# Barometer_022.net
KiCad netlist of a schematic drawn in EAGLE
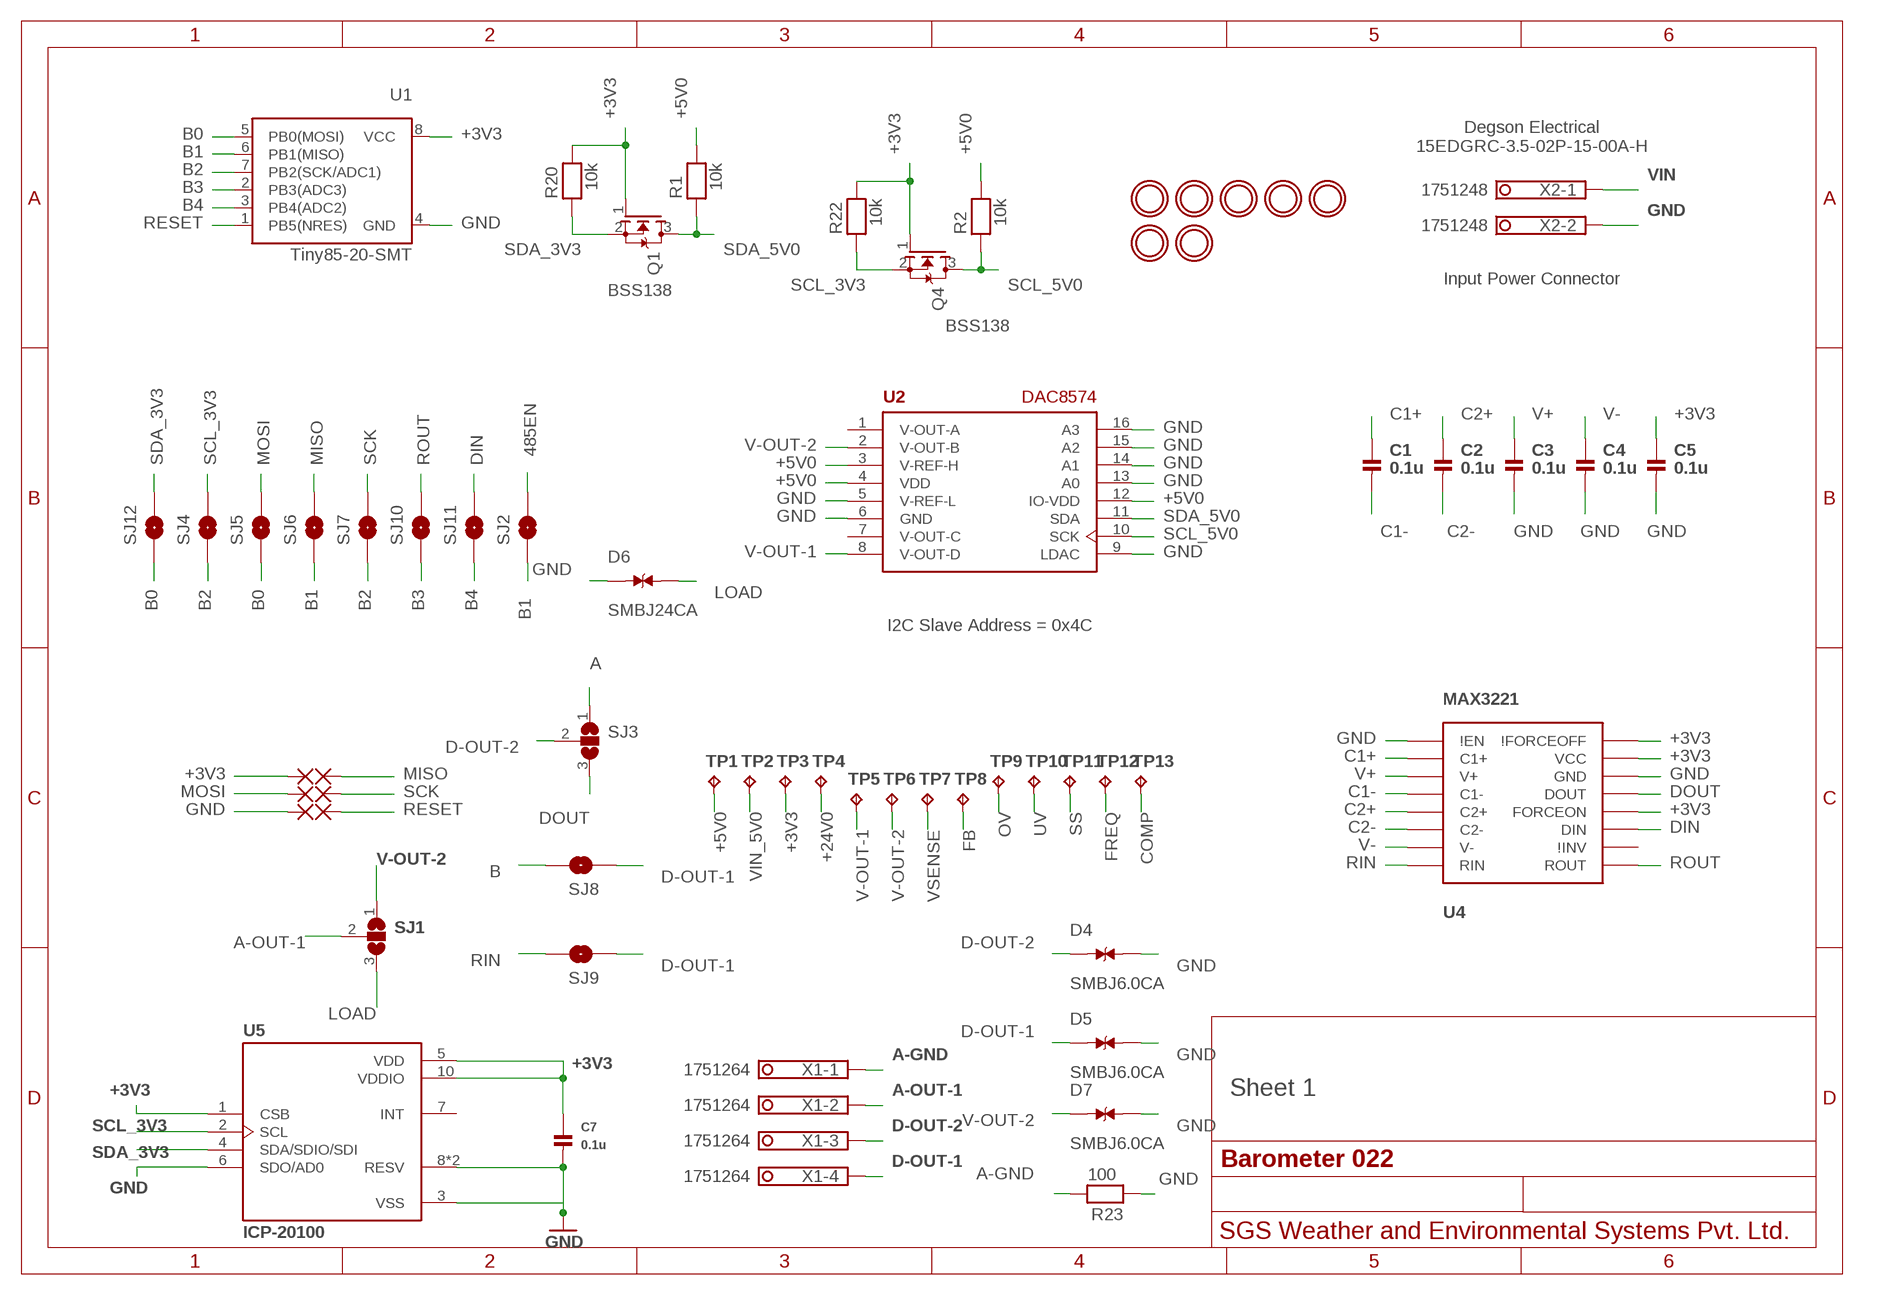
[diagram p0: schematic, sheet 1]
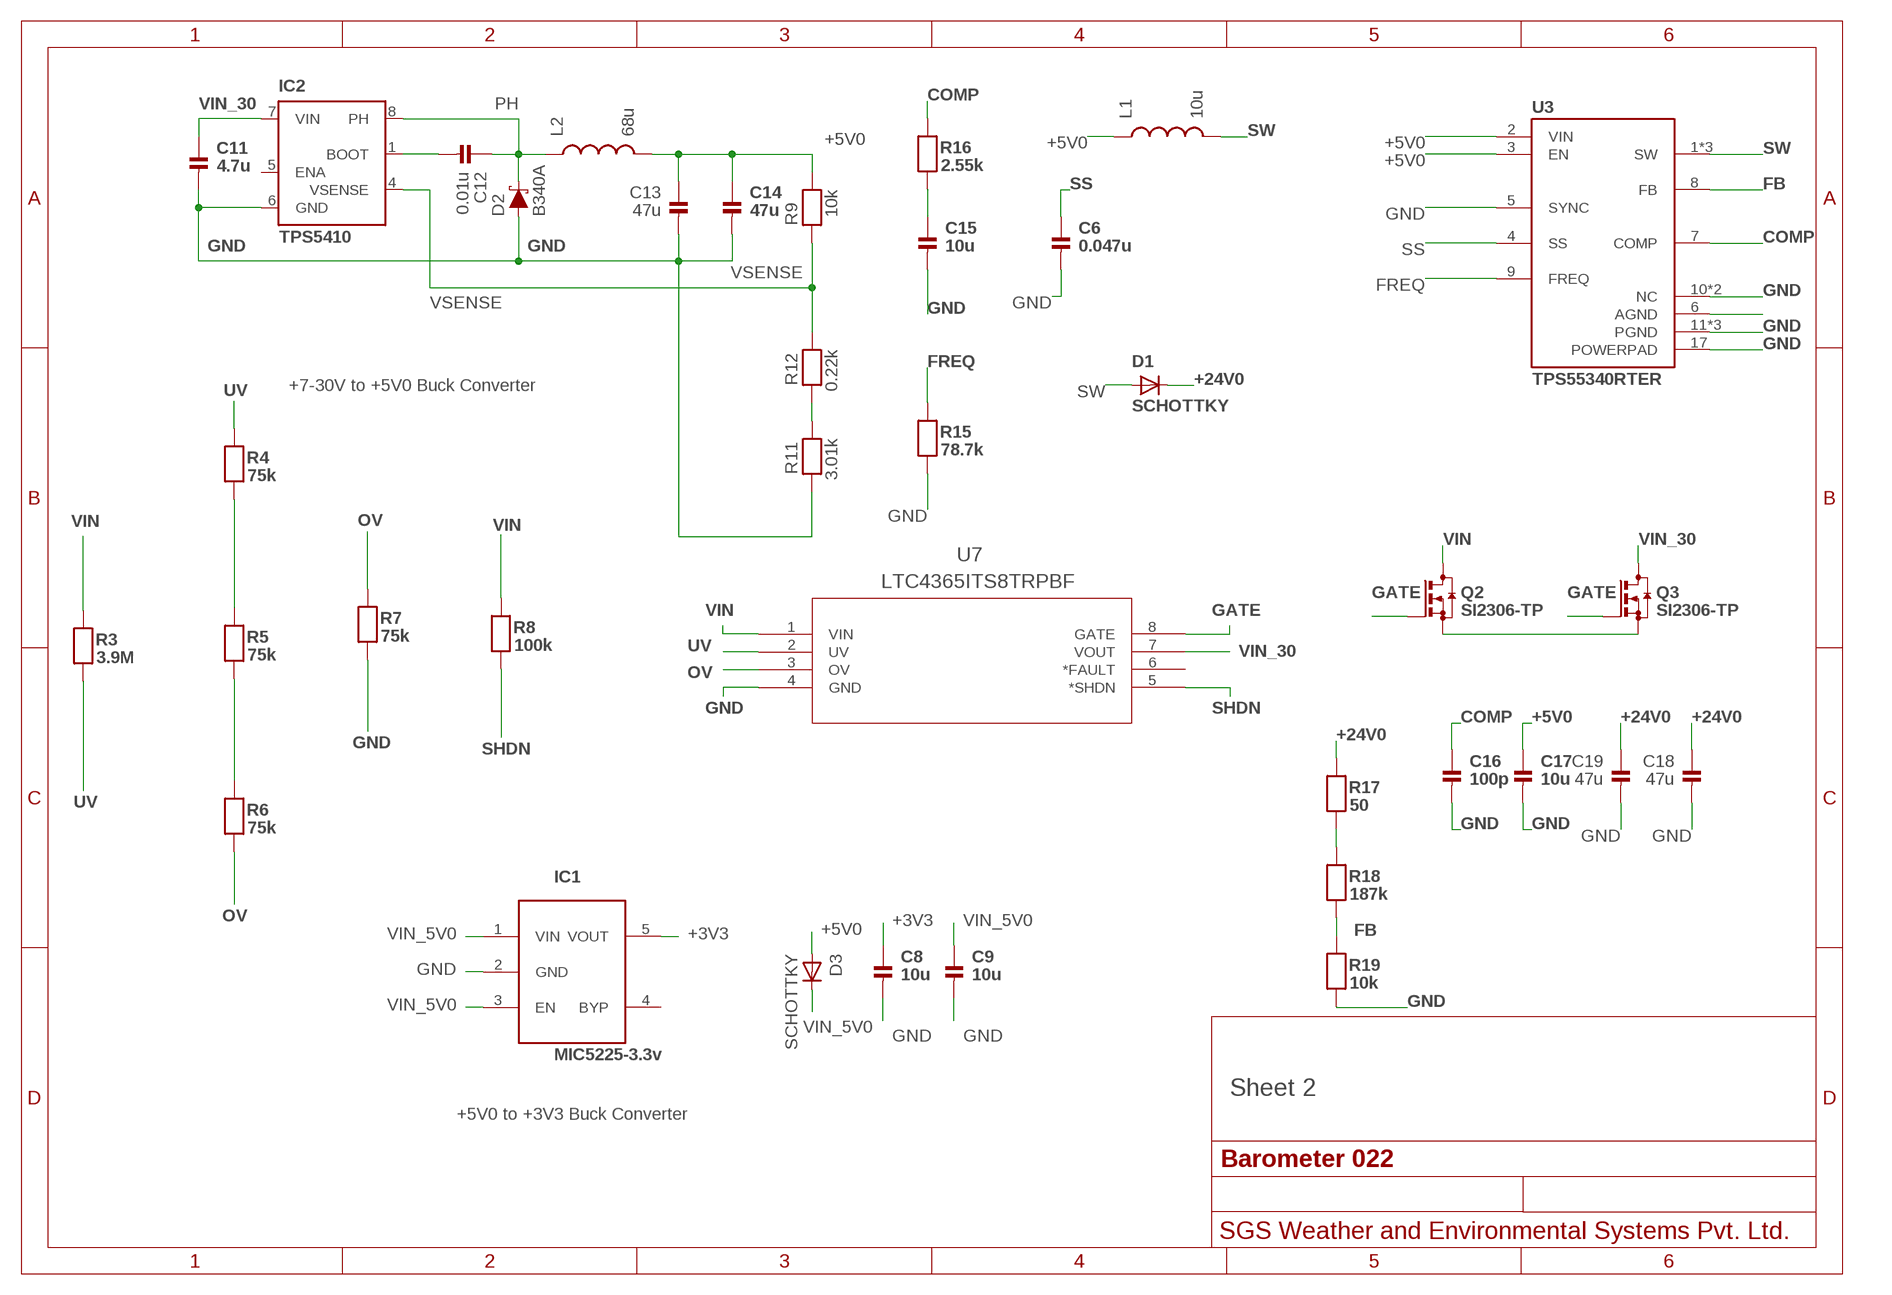
[diagram p1: schematic, sheet 2]
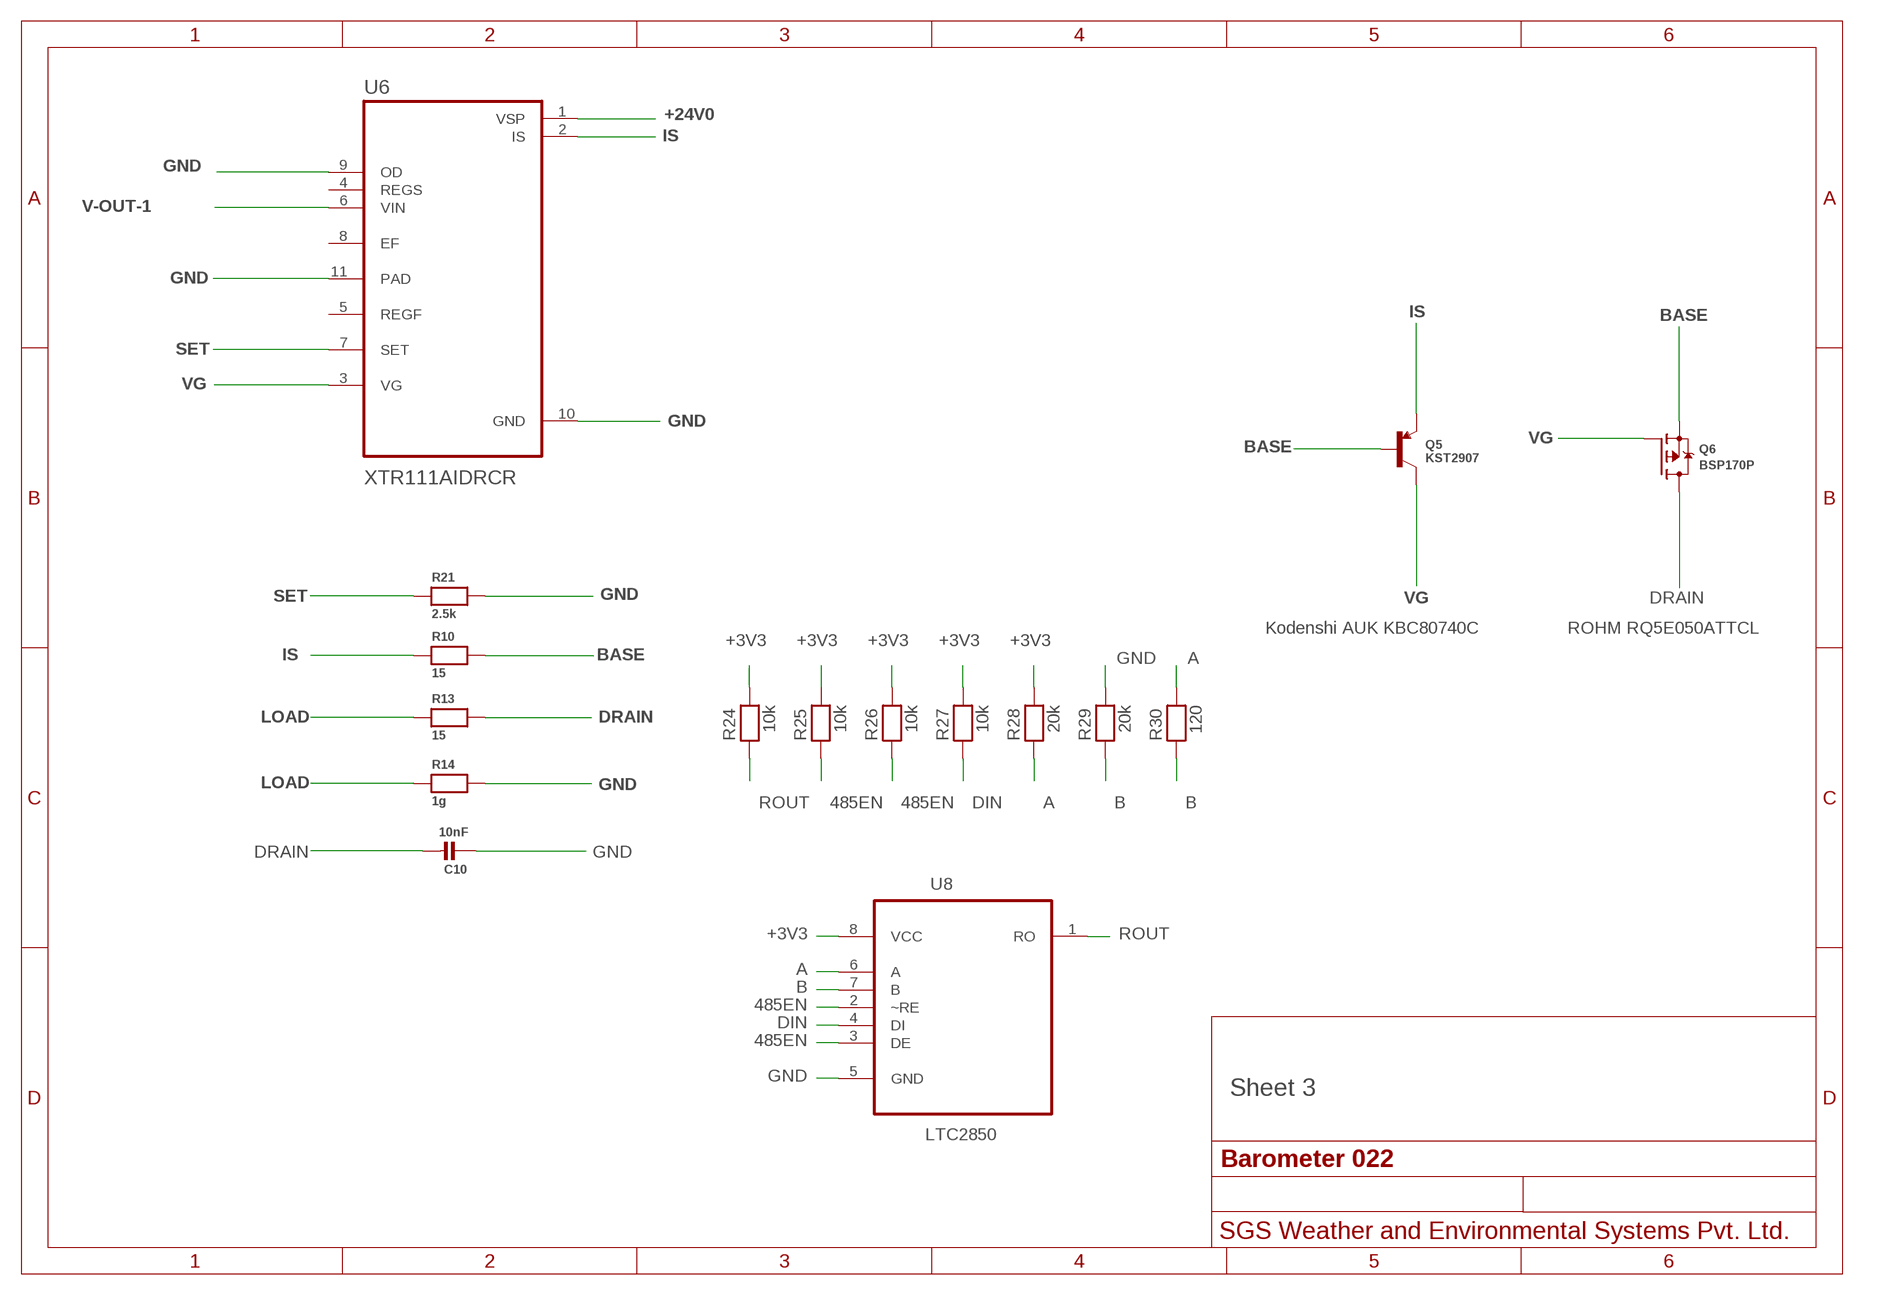
[diagram p2: schematic, sheet 3]
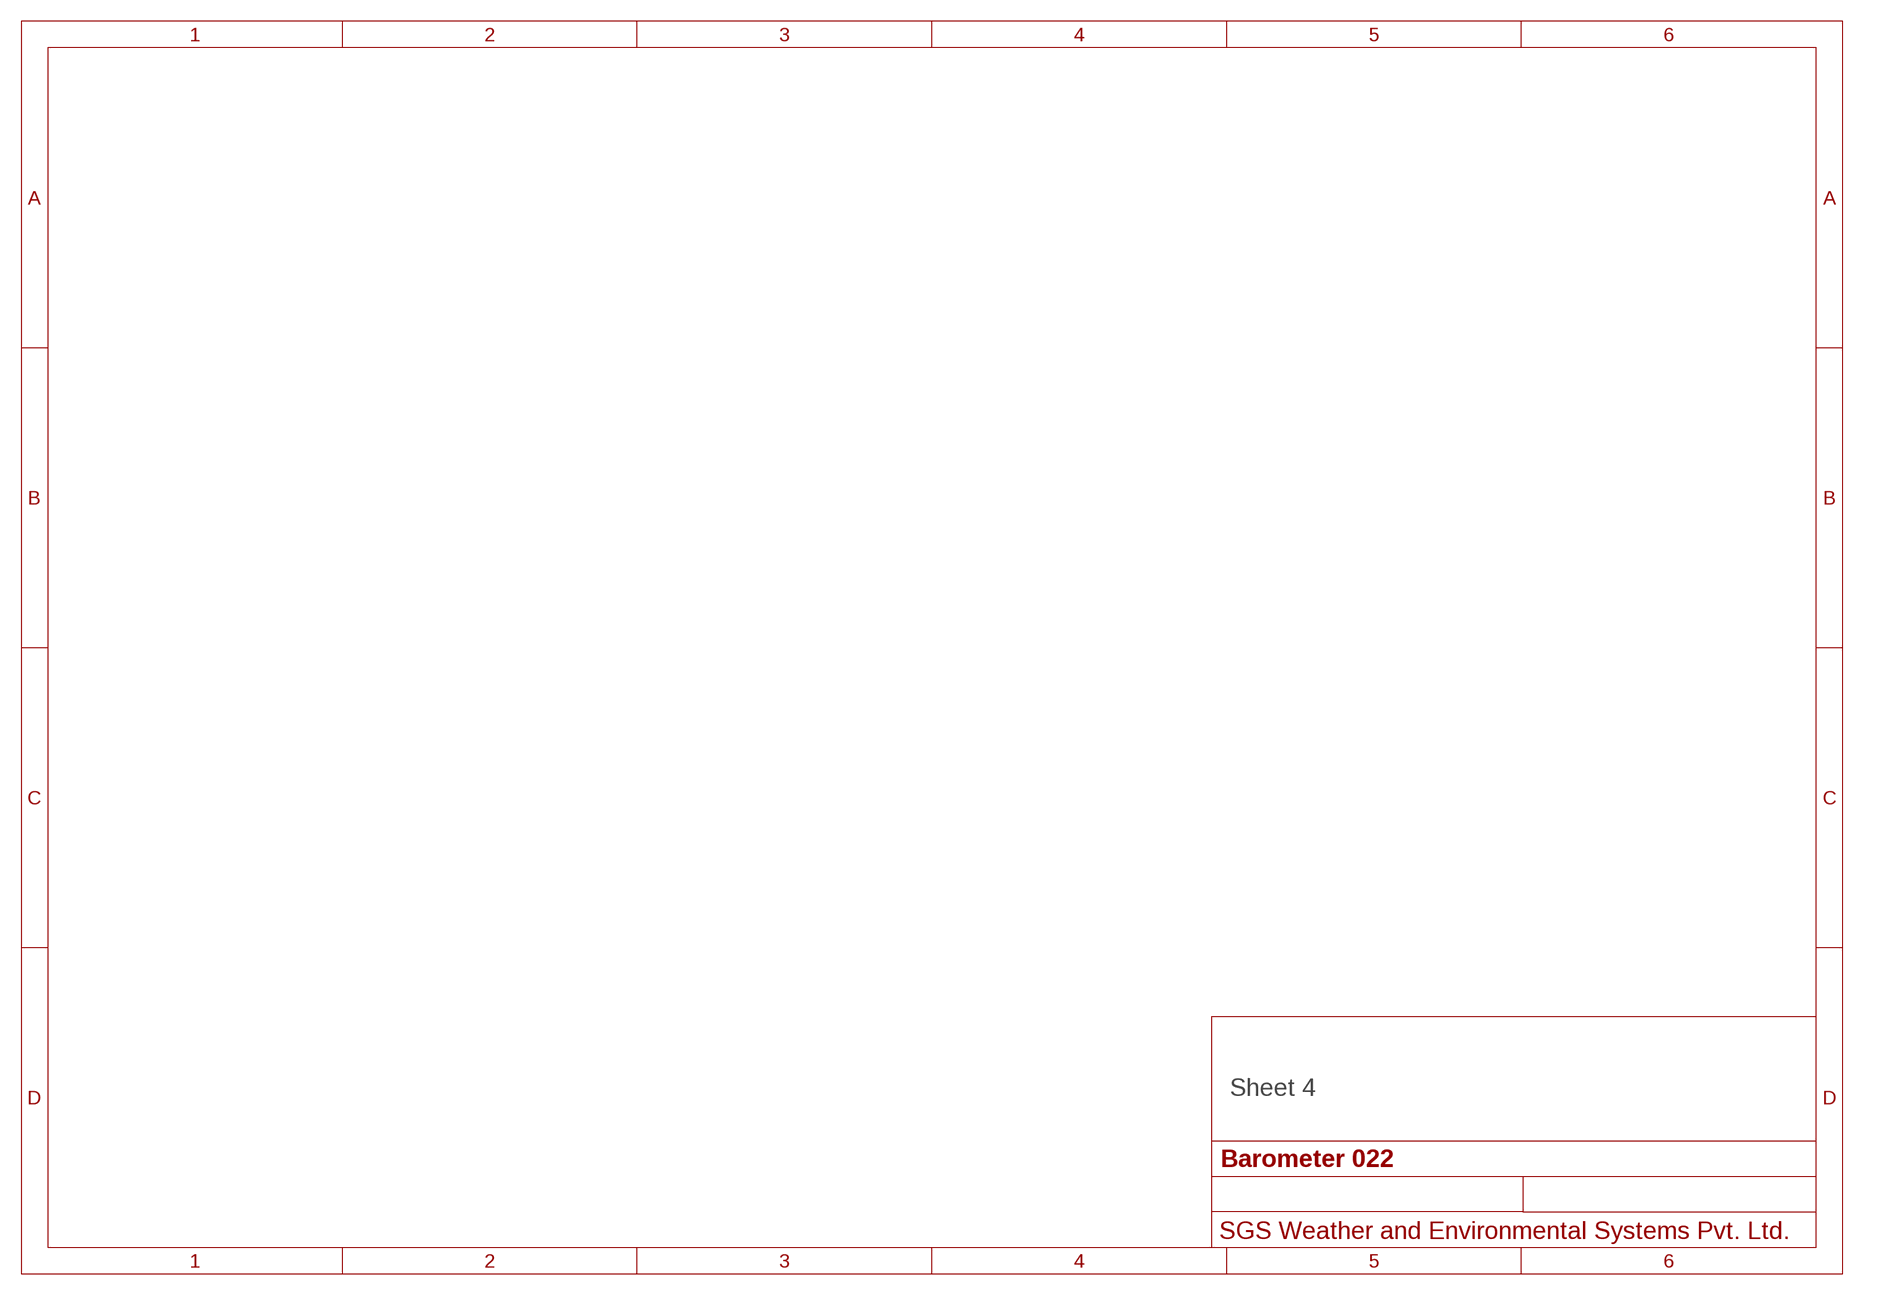
[diagram p3: schematic, sheet 4]

(export (version "E")
  (design (tool "Eeschema 10.0.6"))
  (components
    (comp (ref "C6")
      (value "0.047u")
      (footprint "eagle-import:0603@1")
      (libsource (lib "eagle-import") (part "CAP_CERAMIC0603"))
    )
    (comp (ref "C8")
      (value "10u")
      (footprint "eagle-import:0603@1")
      (libsource (lib "eagle-import") (part "CAP_CERAMIC0603"))
    )
    (comp (ref "C9")
      (value "10u")
      (footprint "eagle-import:0603@1")
      (libsource (lib "eagle-import") (part "CAP_CERAMIC0603"))
    )
    (comp (ref "C11")
      (value "4.7u")
      (footprint "eagle-import:0805@1")
      (libsource (lib "eagle-import") (part "CAP_CERAMIC0805"))
    )
    (comp (ref "C12")
      (value "0.01u")
      (footprint "eagle-import:0603@1")
      (libsource (lib "eagle-import") (part "CAP_CERAMIC0603"))
    )
    (comp (ref "C13")
      (value "47u")
      (footprint "eagle-import:1206@1")
      (libsource (lib "eagle-import") (part "CAP_CERAMIC1206"))
    )
    (comp (ref "C14")
      (value "47u")
      (footprint "eagle-import:1206@1")
      (libsource (lib "eagle-import") (part "CAP_CERAMIC1206"))
    )
    (comp (ref "C15")
      (value "10u")
      (footprint "eagle-import:0603@1")
      (libsource (lib "eagle-import") (part "CAP_CERAMIC0603"))
    )
    (comp (ref "C16")
      (value "100p")
      (footprint "eagle-import:0603@1")
      (libsource (lib "eagle-import") (part "CAP_CERAMIC0603"))
    )
    (comp (ref "C17")
      (value "10u")
      (footprint "eagle-import:0603@1")
      (libsource (lib "eagle-import") (part "CAP_CERAMIC0603"))
    )
    (comp (ref "C18")
      (value "47u")
      (footprint "eagle-import:1206@1")
      (libsource (lib "eagle-import") (part "CAP_CERAMIC1206"))
    )
    (comp (ref "C19")
      (value "47u")
      (footprint "eagle-import:1206@1")
      (libsource (lib "eagle-import") (part "CAP_CERAMIC1206"))
    )
    (comp (ref "D1")
      (value "SCHOTTKY")
      (footprint "eagle-import:SOD-123FL")
      (libsource (lib "eagle-import") (part "DIODE_SOD-123FL"))
    )
    (comp (ref "D2")
      (value "B340A")
      (footprint "eagle-import:SMA-DIODE")
      (libsource (lib "eagle-import") (part "DIODE-SCHOTTKY-B340A"))
    )
    (comp (ref "D3")
      (value "SCHOTTKY")
      (footprint "eagle-import:SOD-123FL")
      (libsource (lib "eagle-import") (part "DIODE_SOD-123FL"))
    )
    (comp (ref "IC1")
      (value "MIC5225-3.3v")
      (footprint "eagle-import:SOT23-5L")
      (libsource (lib "eagle-import") (part "LP298XS"))
    )
    (comp (ref "IC2")
      (value "TPS5410")
      (footprint "eagle-import:D_R-PDSO-G08")
      (fields (field (name "MPN") "TPS5410DR"))
      (libsource (lib "eagle-import") (part "TPS5410"))
    )
    (comp (ref "L1")
      (value "10u")
      (footprint "eagle-import:VLS6045EX")
      (libsource (lib "eagle-import") (part "INDUCTOR-TDKVLS6045EX"))
    )
    (comp (ref "L2")
      (value "68u")
      (footprint "eagle-import:VLS6045EX")
      (libsource (lib "eagle-import") (part "INDUCTOR-TDKVLS6045EX"))
    )
    (comp (ref "Q2")
      (value "SI2306-TP")
      (footprint "eagle-import:SOT23")
      (libsource (lib "eagle-import") (part "BSS123"))
    )
    (comp (ref "Q3")
      (value "SI2306-TP")
      (footprint "eagle-import:SOT23")
      (libsource (lib "eagle-import") (part "BSS123"))
    )
    (comp (ref "R3")
      (value "3.9M")
      (footprint "eagle-import:0603")
      (libsource (lib "eagle-import") (part "RESISTOR0603"))
    )
    (comp (ref "R4")
      (value "75k")
      (footprint "eagle-import:0603")
      (libsource (lib "eagle-import") (part "RESISTOR0603"))
    )
    (comp (ref "R5")
      (value "75k")
      (footprint "eagle-import:0603")
      (libsource (lib "eagle-import") (part "RESISTOR0603"))
    )
    (comp (ref "R6")
      (value "75k")
      (footprint "eagle-import:0603")
      (libsource (lib "eagle-import") (part "RESISTOR0603"))
    )
    (comp (ref "R7")
      (value "75k")
      (footprint "eagle-import:0603")
      (libsource (lib "eagle-import") (part "RESISTOR0603"))
    )
    (comp (ref "R8")
      (value "100k")
      (footprint "eagle-import:0603")
      (libsource (lib "eagle-import") (part "RESISTOR0603"))
    )
    (comp (ref "R9")
      (value "10k")
      (footprint "eagle-import:0603")
      (libsource (lib "eagle-import") (part "RESISTOR0603"))
    )
    (comp (ref "R11")
      (value "3.01k")
      (footprint "eagle-import:0603")
      (libsource (lib "eagle-import") (part "RESISTOR0603"))
    )
    (comp (ref "R12")
      (value "0.22k")
      (footprint "eagle-import:0603")
      (libsource (lib "eagle-import") (part "RESISTOR0603"))
    )
    (comp (ref "R15")
      (value "78.7k")
      (footprint "eagle-import:0603")
      (libsource (lib "eagle-import") (part "RESISTOR0603"))
    )
    (comp (ref "R16")
      (value "2.55k")
      (footprint "eagle-import:0603")
      (libsource (lib "eagle-import") (part "RESISTOR0603"))
    )
    (comp (ref "R17")
      (value "50")
      (footprint "eagle-import:0603")
      (libsource (lib "eagle-import") (part "RESISTOR0603"))
    )
    (comp (ref "R18")
      (value "187k")
      (footprint "eagle-import:0603")
      (libsource (lib "eagle-import") (part "RESISTOR0603"))
    )
    (comp (ref "R19")
      (value "10k")
      (footprint "eagle-import:0603")
      (libsource (lib "eagle-import") (part "RESISTOR0603"))
    )
    (comp (ref "U3")
      (value "TPS55340RTER")
      (footprint "eagle-import:QFN50P300X300X80-17N")
      (fields (field (name "MF") "Texas Instruments"))
      (libsource (lib "eagle-import") (part "TPS55340RTER"))
    )
    (comp (ref "U7")
      (value "LTC4365ITS8TRPBF")
      (footprint "eagle-import:TSOT-23_TS8")
      (fields (field (name "MF") "Analog Devices") (field (name "MP") "LTC4365ITS8#TRPBF"))
      (libsource (lib "eagle-import") (part "LTC4365ITS8TRPBF"))
    )
    (comp (ref "C1")
      (value "0.1u")
      (footprint "eagle-import:0603@1")
      (libsource (lib "eagle-import") (part "CAP_CERAMIC0603"))
    )
    (comp (ref "C2")
      (value "0.1u")
      (footprint "eagle-import:0603@1")
      (libsource (lib "eagle-import") (part "CAP_CERAMIC0603"))
    )
    (comp (ref "C3")
      (value "0.1u")
      (footprint "eagle-import:0603@1")
      (libsource (lib "eagle-import") (part "CAP_CERAMIC0603"))
    )
    (comp (ref "C4")
      (value "0.1u")
      (footprint "eagle-import:0603@1")
      (libsource (lib "eagle-import") (part "CAP_CERAMIC0603"))
    )
    (comp (ref "C5")
      (value "0.1u")
      (footprint "eagle-import:0603@1")
      (libsource (lib "eagle-import") (part "CAP_CERAMIC0603"))
    )
    (comp (ref "C7")
      (value "0.1u")
      (footprint "eagle-import:0603@1")
      (libsource (lib "eagle-import") (part "CAP_CERAMIC0603"))
    )
    (comp (ref "D4")
      (value "SMBJ6.0CA")
      (footprint "eagle-import:DIOM4336X265N")
      (fields (field (name "MF") "Bourns"))
      (libsource (lib "eagle-import") (part "SMBJ6.0CA"))
    )
    (comp (ref "D5")
      (value "SMBJ6.0CA")
      (footprint "eagle-import:DIOM4336X265N")
      (fields (field (name "MF") "Bourns"))
      (libsource (lib "eagle-import") (part "SMBJ6.0CA"))
    )
    (comp (ref "D6")
      (value "SMBJ24CA")
      (footprint "eagle-import:DIOM4336X265N")
      (fields
        (field (name "DIGI-KEY_PART_NUMBER") "SMBJ24CAFSTR-ND")
        (field (name "MF") "Taiwan Semiconductor")
      )
      (libsource (lib "eagle-import") (part "SMBJ24CA"))
    )
    (comp (ref "D7")
      (value "SMBJ6.0CA")
      (footprint "eagle-import:DIOM4336X265N")
      (fields (field (name "MF") "Bourns"))
      (libsource (lib "eagle-import") (part "SMBJ6.0CA"))
    )
    (comp (ref "PAD1")
      (value "SMD2")
      (footprint "eagle-import:SMD1,27-2,54")
      (libsource (lib "eagle-import") (part "SMD2"))
    )
    (comp (ref "PAD2")
      (value "SMD2")
      (footprint "eagle-import:SMD1,27-2,54")
      (libsource (lib "eagle-import") (part "SMD2"))
    )
    (comp (ref "PAD3")
      (value "SMD2")
      (footprint "eagle-import:SMD1,27-2,54")
      (libsource (lib "eagle-import") (part "SMD2"))
    )
    (comp (ref "PAD4")
      (value "SMD2")
      (footprint "eagle-import:SMD1,27-2,54")
      (libsource (lib "eagle-import") (part "SMD2"))
    )
    (comp (ref "PAD5")
      (value "SMD2")
      (footprint "eagle-import:SMD1,27-2,54")
      (libsource (lib "eagle-import") (part "SMD2"))
    )
    (comp (ref "PAD6")
      (value "SMD2")
      (footprint "eagle-import:SMD1,27-2,54")
      (libsource (lib "eagle-import") (part "SMD2"))
    )
    (comp (ref "Q1")
      (value "MOSFET-NWIDE")
      (footprint "eagle-import:SOT23-WIDE")
      (libsource (lib "eagle-import") (part "MOSFET-NWIDE"))
    )
    (comp (ref "Q4")
      (value "MOSFET-NWIDE")
      (footprint "eagle-import:SOT23-WIDE")
      (libsource (lib "eagle-import") (part "MOSFET-NWIDE"))
    )
    (comp (ref "R1")
      (value "10k")
      (footprint "eagle-import:0603")
      (libsource (lib "eagle-import") (part "RESISTOR0603"))
    )
    (comp (ref "R2")
      (value "10k")
      (footprint "eagle-import:0603")
      (libsource (lib "eagle-import") (part "RESISTOR0603"))
    )
    (comp (ref "R20")
      (value "10k")
      (footprint "eagle-import:0603")
      (libsource (lib "eagle-import") (part "RESISTOR0603"))
    )
    (comp (ref "R22")
      (value "10k")
      (footprint "eagle-import:0603")
      (libsource (lib "eagle-import") (part "RESISTOR0603"))
    )
    (comp (ref "R23")
      (value "100")
      (footprint "eagle-import:0603")
      (libsource (lib "eagle-import") (part "RESISTOR0603"))
    )
    (comp (ref "SJ1")
      (value "SJ2WW")
      (footprint "eagle-import:SJ_2W")
      (libsource (lib "eagle-import") (part "SJ2WW"))
    )
    (comp (ref "SJ2")
      (value "SOLDERJUMPERTRACE")
      (footprint "eagle-import:SJ_2S-TRACE")
      (libsource (lib "eagle-import") (part "SOLDERJUMPERTRACE"))
    )
    (comp (ref "SJ3")
      (value "SJ2W")
      (footprint "eagle-import:SJ_2")
      (libsource (lib "eagle-import") (part "SJ2W"))
    )
    (comp (ref "SJ4")
      (value "SOLDERJUMPERTRACE")
      (footprint "eagle-import:SJ_2S-TRACE")
      (libsource (lib "eagle-import") (part "SOLDERJUMPERTRACE"))
    )
    (comp (ref "SJ5")
      (value "SOLDERJUMPERTRACE")
      (footprint "eagle-import:SJ_2S-TRACE")
      (libsource (lib "eagle-import") (part "SOLDERJUMPERTRACE"))
    )
    (comp (ref "SJ6")
      (value "SOLDERJUMPERTRACE")
      (footprint "eagle-import:SJ_2S-TRACE")
      (libsource (lib "eagle-import") (part "SOLDERJUMPERTRACE"))
    )
    (comp (ref "SJ7")
      (value "SOLDERJUMPERTRACE")
      (footprint "eagle-import:SJ_2S-TRACE")
      (libsource (lib "eagle-import") (part "SOLDERJUMPERTRACE"))
    )
    (comp (ref "SJ8")
      (value "SOLDERJUMPERTRACE")
      (footprint "eagle-import:SJ_2S-TRACE")
      (libsource (lib "eagle-import") (part "SOLDERJUMPERTRACE"))
    )
    (comp (ref "SJ9")
      (value "SOLDERJUMPERTRACE")
      (footprint "eagle-import:SJ_2S-TRACE")
      (libsource (lib "eagle-import") (part "SOLDERJUMPERTRACE"))
    )
    (comp (ref "SJ10")
      (value "SOLDERJUMPERTRACE")
      (footprint "eagle-import:SJ_2S-TRACE")
      (libsource (lib "eagle-import") (part "SOLDERJUMPERTRACE"))
    )
    (comp (ref "SJ11")
      (value "SOLDERJUMPERTRACE")
      (footprint "eagle-import:SJ_2S-TRACE")
      (libsource (lib "eagle-import") (part "SOLDERJUMPERTRACE"))
    )
    (comp (ref "SJ12")
      (value "SOLDERJUMPERNO")
      (footprint "eagle-import:SJ_2S-NO")
      (libsource (lib "eagle-import") (part "SOLDERJUMPERNO"))
    )
    (comp (ref "TP1")
      (value "TPB1,27")
      (footprint "eagle-import:B1,27")
      (libsource (lib "eagle-import") (part "TPB1,27"))
    )
    (comp (ref "TP2")
      (value "TPB1,27")
      (footprint "eagle-import:B1,27")
      (libsource (lib "eagle-import") (part "TPB1,27"))
    )
    (comp (ref "TP3")
      (value "TPB1,27")
      (footprint "eagle-import:B1,27")
      (libsource (lib "eagle-import") (part "TPB1,27"))
    )
    (comp (ref "TP4")
      (value "TPB1,27")
      (footprint "eagle-import:B1,27")
      (libsource (lib "eagle-import") (part "TPB1,27"))
    )
    (comp (ref "TP5")
      (value "TPB1,27")
      (footprint "eagle-import:B1,27")
      (libsource (lib "eagle-import") (part "TPB1,27"))
    )
    (comp (ref "TP6")
      (value "TPB1,27")
      (footprint "eagle-import:B1,27")
      (libsource (lib "eagle-import") (part "TPB1,27"))
    )
    (comp (ref "TP7")
      (value "TPB1,27")
      (footprint "eagle-import:B1,27")
      (libsource (lib "eagle-import") (part "TPB1,27"))
    )
    (comp (ref "TP8")
      (value "TPB1,27")
      (footprint "eagle-import:B1,27")
      (libsource (lib "eagle-import") (part "TPB1,27"))
    )
    (comp (ref "TP9")
      (value "TPB1,27")
      (footprint "eagle-import:B1,27")
      (libsource (lib "eagle-import") (part "TPB1,27"))
    )
    (comp (ref "TP10")
      (value "TPB1,27")
      (footprint "eagle-import:B1,27")
      (libsource (lib "eagle-import") (part "TPB1,27"))
    )
    (comp (ref "TP11")
      (value "TPB1,27")
      (footprint "eagle-import:B1,27")
      (libsource (lib "eagle-import") (part "TPB1,27"))
    )
    (comp (ref "TP12")
      (value "TPB1,27")
      (footprint "eagle-import:B1,27")
      (libsource (lib "eagle-import") (part "TPB1,27"))
    )
    (comp (ref "TP13")
      (value "TPB1,27")
      (footprint "eagle-import:B1,27")
      (libsource (lib "eagle-import") (part "TPB1,27"))
    )
    (comp (ref "U$1")
      (value "MOUNTINGHOLE3.0THIN")
      (footprint "eagle-import:MOUNTINGHOLE_3.0_PLATEDTHIN")
      (libsource (lib "eagle-import") (part "MOUNTINGHOLE3.0THIN"))
    )
    (comp (ref "U$2")
      (value "MOUNTINGHOLE3.0THIN")
      (footprint "eagle-import:MOUNTINGHOLE_3.0_PLATEDTHIN")
      (libsource (lib "eagle-import") (part "MOUNTINGHOLE3.0THIN"))
    )
    (comp (ref "U$3")
      (value "MOUNTINGHOLE3.0THIN")
      (footprint "eagle-import:MOUNTINGHOLE_3.0_PLATEDTHIN")
      (libsource (lib "eagle-import") (part "MOUNTINGHOLE3.0THIN"))
    )
    (comp (ref "U$4")
      (value "MOUNTINGHOLE3.0THIN")
      (footprint "eagle-import:MOUNTINGHOLE_3.0_PLATEDTHIN")
      (libsource (lib "eagle-import") (part "MOUNTINGHOLE3.0THIN"))
    )
    (comp (ref "U$5")
      (value "MOUNTINGHOLE3.0THIN")
      (footprint "eagle-import:MOUNTINGHOLE_3.0_PLATEDTHIN")
      (libsource (lib "eagle-import") (part "MOUNTINGHOLE3.0THIN"))
    )
    (comp (ref "U$6")
      (value "MOUNTINGHOLE3.0THIN")
      (footprint "eagle-import:MOUNTINGHOLE_3.0_PLATEDTHIN")
      (libsource (lib "eagle-import") (part "MOUNTINGHOLE3.0THIN"))
    )
    (comp (ref "U$7")
      (value "MOUNTINGHOLE3.0THIN")
      (footprint "eagle-import:MOUNTINGHOLE_3.0_PLATEDTHIN")
      (libsource (lib "eagle-import") (part "MOUNTINGHOLE3.0THIN"))
    )
    (comp (ref "U1")
      (value "Tiny85-20-SMT")
      (footprint "eagle-import:SO08-EIAJ_MCU")
      (libsource (lib "eagle-import") (part "ATTINY45TINY85-20-SMT"))
    )
    (comp (ref "U2")
      (value "DAC8574")
      (footprint "eagle-import:TSSOP16")
      (libsource (lib "eagle-import") (part "DAC8574"))
    )
    (comp (ref "U4")
      (value "MAX3221")
      (footprint "eagle-import:TSSOP16")
      (libsource (lib "eagle-import") (part "MAX3221-TSSOP16"))
    )
    (comp (ref "U5")
      (value "ICP-20100")
      (footprint "eagle-import:PQFN50P200X200X85-10N")
      (fields (field (name "MF") "TDK InvenSense"))
      (libsource (lib "eagle-import") (part "ICP-20100"))
    )
    (comp (ref "X1")
      (value "1751264")
      (footprint "eagle-import:1751264")
      (libsource (lib "eagle-import") (part "1751264"))
    )
    (comp (ref "X2")
      (value "1751248")
      (footprint "eagle-import:1751248")
      (libsource (lib "eagle-import") (part "1751248"))
    )
    (comp (ref "C10")
      (value "10nF")
      (footprint "eagle-import:0603@1")
      (libsource (lib "eagle-import") (part "CAP_CERAMIC0603"))
    )
    (comp (ref "Q5")
      (value "KST2907")
      (footprint "eagle-import:SOT23-R")
      (libsource (lib "eagle-import") (part "TRANSISTOR_PNPSOT23-REFLOW"))
    )
    (comp (ref "Q6")
      (value "BSP170P")
      (footprint "eagle-import:SOT23-R")
      (libsource (lib "eagle-import") (part "MOSFET-P"))
    )
    (comp (ref "R10")
      (value "15")
      (footprint "eagle-import:0603")
      (libsource (lib "eagle-import") (part "RESISTOR0603"))
    )
    (comp (ref "R13")
      (value "15")
      (footprint "eagle-import:0603")
      (libsource (lib "eagle-import") (part "RESISTOR0603"))
    )
    (comp (ref "R14")
      (value "1g")
      (footprint "eagle-import:0603")
      (libsource (lib "eagle-import") (part "RESISTOR0603"))
    )
    (comp (ref "R21")
      (value "2.5k")
      (footprint "eagle-import:0603")
      (libsource (lib "eagle-import") (part "RESISTOR0603"))
    )
    (comp (ref "R24")
      (value "10k")
      (footprint "eagle-import:0603")
      (libsource (lib "eagle-import") (part "RESISTOR0603"))
    )
    (comp (ref "R25")
      (value "10k")
      (footprint "eagle-import:0603")
      (libsource (lib "eagle-import") (part "RESISTOR0603"))
    )
    (comp (ref "R26")
      (value "10k")
      (footprint "eagle-import:0603")
      (libsource (lib "eagle-import") (part "RESISTOR0603"))
    )
    (comp (ref "R27")
      (value "10k")
      (footprint "eagle-import:0603")
      (libsource (lib "eagle-import") (part "RESISTOR0603"))
    )
    (comp (ref "R28")
      (value "20k")
      (footprint "eagle-import:0603")
      (libsource (lib "eagle-import") (part "RESISTOR0603"))
    )
    (comp (ref "R29")
      (value "20k")
      (footprint "eagle-import:0603")
      (libsource (lib "eagle-import") (part "RESISTOR0603"))
    )
    (comp (ref "R30")
      (value "120")
      (footprint "eagle-import:0603")
      (libsource (lib "eagle-import") (part "RESISTOR0603"))
    )
    (comp (ref "U6")
      (value "XTR111AIDRCR")
      (footprint "eagle-import:VREG_V62_16624-01YE")
      (fields (field (name "MF") "Texas Instruments"))
      (libsource (lib "eagle-import") (part "XTR111AIDRCR"))
    )
    (comp (ref "U8")
      (value "LTC2850")
      (footprint "eagle-import:SOIC127P600X175-8N")
      (fields (field (name "MPN") "LTC2850IS8#PBF"))
      (libsource (lib "eagle-import") (part "LTC2850IS8PBF"))
    )
  )
  (nets
    (net (code "1") (name "+3V3") (class "Default")
      (node (ref "C5") (pin "1") (pinfunction "P$1_1") (pintype "passive"))
      (node (ref "C7") (pin "1") (pinfunction "P$1_1") (pintype "passive"))
      (node (ref "C8") (pin "1") (pinfunction "P$1_1") (pintype "passive"))
      (node (ref "IC1") (pin "5") (pinfunction "VOUT_5") (pintype "bidirectional"))
      (node (ref "PAD1") (pin "1") (pinfunction "P_1") (pintype "passive"))
      (node (ref "Q1") (pin "1") (pinfunction "G_1") (pintype "bidirectional"))
      (node (ref "Q4") (pin "1") (pinfunction "G_1") (pintype "bidirectional"))
      (node (ref "R20") (pin "2") (pinfunction "2_2") (pintype "passive"))
      (node (ref "R22") (pin "2") (pinfunction "2_2") (pintype "passive"))
      (node (ref "R24") (pin "2") (pinfunction "2_2") (pintype "passive"))
      (node (ref "R25") (pin "2") (pinfunction "2_2") (pintype "passive"))
      (node (ref "R26") (pin "2") (pinfunction "2_2") (pintype "passive"))
      (node (ref "R27") (pin "2") (pinfunction "2_2") (pintype "passive"))
      (node (ref "R28") (pin "2") (pinfunction "2_2") (pintype "passive"))
      (node (ref "TP3") (pin "TP") (pinfunction "TP_TP") (pintype "input"))
      (node (ref "U1") (pin "8") (pinfunction "VCC_8") (pintype "bidirectional"))
      (node (ref "U4") (pin "12") (pinfunction "FORCEON_12") (pintype "bidirectional"))
      (node (ref "U4") (pin "15") (pinfunction "VCC_15") (pintype "bidirectional"))
      (node (ref "U4") (pin "16") (pinfunction "\\~{FORCEOFF}_16") (pintype "bidirectional"))
      (node (ref "U5") (pin "1") (pinfunction "CSB_1") (pintype "input"))
      (node (ref "U5") (pin "10") (pinfunction "VDDIO_10") (pintype "power_in"))
      (node (ref "U5") (pin "5") (pinfunction "VDD_5") (pintype "power_in"))
      (node (ref "U8") (pin "8") (pinfunction "VCC_8") (pintype "power_in"))
    )
    (net (code "2") (name "+5V0") (class "Default")
      (node (ref "C13") (pin "1") (pinfunction "P$1_1") (pintype "passive"))
      (node (ref "C14") (pin "1") (pinfunction "P$1_1") (pintype "passive"))
      (node (ref "C17") (pin "1") (pinfunction "P$1_1") (pintype "passive"))
      (node (ref "D3") (pin "A") (pinfunction "A_A") (pintype "passive"))
      (node (ref "L1") (pin "1") (pinfunction "1_1") (pintype "passive"))
      (node (ref "L2") (pin "2") (pinfunction "2_2") (pintype "passive"))
      (node (ref "R1") (pin "2") (pinfunction "2_2") (pintype "passive"))
      (node (ref "R2") (pin "2") (pinfunction "2_2") (pintype "passive"))
      (node (ref "R9") (pin "2") (pinfunction "2_2") (pintype "passive"))
      (node (ref "TP1") (pin "TP") (pinfunction "TP_TP") (pintype "input"))
      (node (ref "U2") (pin "12") (pinfunction "IO-VDD_12") (pintype "power_in"))
      (node (ref "U2") (pin "3") (pinfunction "V-REF-H_3") (pintype "input"))
      (node (ref "U2") (pin "4") (pinfunction "VDD_4") (pintype "power_in"))
      (node (ref "U3") (pin "2") (pinfunction "VIN_2") (pintype "power_in"))
      (node (ref "U3") (pin "3") (pinfunction "EN_3") (pintype "input"))
    )
    (net (code "3") (name "+24V0") (class "Default")
      (node (ref "C18") (pin "1") (pinfunction "P$1_1") (pintype "passive"))
      (node (ref "C19") (pin "1") (pinfunction "P$1_1") (pintype "passive"))
      (node (ref "D1") (pin "C") (pinfunction "C_C") (pintype "passive"))
      (node (ref "R17") (pin "2") (pinfunction "2_2") (pintype "passive"))
      (node (ref "TP4") (pin "TP") (pinfunction "TP_TP") (pintype "input"))
      (node (ref "U6") (pin "1") (pinfunction "VSP_1") (pintype "power_in"))
    )
    (net (code "4") (name "485EN") (class "Default")
      (node (ref "R25") (pin "1") (pinfunction "1_1") (pintype "passive"))
      (node (ref "R26") (pin "1") (pinfunction "1_1") (pintype "passive"))
      (node (ref "SJ2") (pin "2") (pinfunction "2_2") (pintype "passive"))
      (node (ref "U8") (pin "2") (pinfunction "~{RE}_2") (pintype "input"))
      (node (ref "U8") (pin "3") (pinfunction "DE_3") (pintype "input"))
    )
    (net (code "5") (name "A") (class "Default")
      (node (ref "R28") (pin "1") (pinfunction "1_1") (pintype "passive"))
      (node (ref "R30") (pin "2") (pinfunction "2_2") (pintype "passive"))
      (node (ref "SJ3") (pin "1") (pinfunction "1_1") (pintype "passive"))
      (node (ref "U8") (pin "6") (pinfunction "A_6") (pintype "input"))
    )
    (net (code "6") (name "A-GND") (class "Default")
      (node (ref "R23") (pin "2") (pinfunction "2_2") (pintype "passive"))
      (node (ref "X1") (pin "1") (pinfunction "K_1") (pintype "passive"))
    )
    (net (code "7") (name "A-OUT-1") (class "Default")
      (node (ref "SJ1") (pin "2") (pinfunction "2_2") (pintype "passive"))
      (node (ref "X1") (pin "2") (pinfunction "K_2") (pintype "passive"))
    )
    (net (code "8") (name "B") (class "Default")
      (node (ref "R29") (pin "1") (pinfunction "1_1") (pintype "passive"))
      (node (ref "R30") (pin "1") (pinfunction "1_1") (pintype "passive"))
      (node (ref "SJ8") (pin "2") (pinfunction "2_2") (pintype "passive"))
      (node (ref "U8") (pin "7") (pinfunction "B_7") (pintype "input"))
    )
    (net (code "9") (name "B0") (class "Default")
      (node (ref "SJ12") (pin "1") (pinfunction "1_1") (pintype "passive"))
      (node (ref "SJ5") (pin "1") (pinfunction "1_1") (pintype "passive"))
      (node (ref "U1") (pin "5") (pinfunction "PB0(MOSI)_5") (pintype "bidirectional"))
    )
    (net (code "10") (name "B1") (class "Default")
      (node (ref "SJ2") (pin "1") (pinfunction "1_1") (pintype "passive"))
      (node (ref "SJ6") (pin "1") (pinfunction "1_1") (pintype "passive"))
      (node (ref "U1") (pin "6") (pinfunction "PB1(MISO)_6") (pintype "bidirectional"))
    )
    (net (code "11") (name "B2") (class "Default")
      (node (ref "SJ4") (pin "1") (pinfunction "1_1") (pintype "passive"))
      (node (ref "SJ7") (pin "1") (pinfunction "1_1") (pintype "passive"))
      (node (ref "U1") (pin "7") (pinfunction "PB2(SCK/ADC1)_7") (pintype "bidirectional"))
    )
    (net (code "12") (name "B3") (class "Default")
      (node (ref "SJ10") (pin "1") (pinfunction "1_1") (pintype "passive"))
      (node (ref "U1") (pin "2") (pinfunction "PB3(ADC3)_2") (pintype "bidirectional"))
    )
    (net (code "13") (name "B4") (class "Default")
      (node (ref "SJ11") (pin "1") (pinfunction "1_1") (pintype "passive"))
      (node (ref "U1") (pin "3") (pinfunction "PB4(ADC2)_3") (pintype "bidirectional"))
    )
    (net (code "14") (name "BASE") (class "Default")
      (node (ref "Q5") (pin "1") (pinfunction "B_1") (pintype "passive"))
      (node (ref "Q6") (pin "2") (pinfunction "S_2") (pintype "passive"))
      (node (ref "R10") (pin "2") (pinfunction "2_2") (pintype "passive"))
    )
    (net (code "15") (name "C1+") (class "Default")
      (node (ref "C1") (pin "1") (pinfunction "P$1_1") (pintype "passive"))
      (node (ref "U4") (pin "2") (pinfunction "C1+_2") (pintype "bidirectional"))
    )
    (net (code "16") (name "C1-") (class "Default")
      (node (ref "C1") (pin "2") (pinfunction "P$2_2") (pintype "passive"))
      (node (ref "U4") (pin "4") (pinfunction "C1-_4") (pintype "bidirectional"))
    )
    (net (code "17") (name "C2+") (class "Default")
      (node (ref "C2") (pin "1") (pinfunction "P$1_1") (pintype "passive"))
      (node (ref "U4") (pin "5") (pinfunction "C2+_5") (pintype "bidirectional"))
    )
    (net (code "18") (name "C2-") (class "Default")
      (node (ref "C2") (pin "2") (pinfunction "P$2_2") (pintype "passive"))
      (node (ref "U4") (pin "6") (pinfunction "C2-_6") (pintype "bidirectional"))
    )
    (net (code "19") (name "COMP") (class "Default")
      (node (ref "C16") (pin "1") (pinfunction "P$1_1") (pintype "passive"))
      (node (ref "R16") (pin "2") (pinfunction "2_2") (pintype "passive"))
      (node (ref "TP13") (pin "TP") (pinfunction "TP_TP") (pintype "input"))
      (node (ref "U3") (pin "7") (pinfunction "COMP_7") (pintype "output"))
    )
    (net (code "20") (name "D-OUT-1") (class "Default")
      (node (ref "D5") (pin "1") (pinfunction "1_1") (pintype "passive"))
      (node (ref "SJ8") (pin "1") (pinfunction "1_1") (pintype "passive"))
      (node (ref "SJ9") (pin "1") (pinfunction "1_1") (pintype "passive"))
      (node (ref "X1") (pin "4") (pinfunction "K_4") (pintype "passive"))
    )
    (net (code "21") (name "D-OUT-2") (class "Default")
      (node (ref "D4") (pin "1") (pinfunction "1_1") (pintype "passive"))
      (node (ref "SJ3") (pin "2") (pinfunction "2_2") (pintype "passive"))
      (node (ref "X1") (pin "3") (pinfunction "K_3") (pintype "passive"))
    )
    (net (code "22") (name "DIN") (class "Default")
      (node (ref "R27") (pin "1") (pinfunction "1_1") (pintype "passive"))
      (node (ref "SJ11") (pin "2") (pinfunction "2_2") (pintype "passive"))
      (node (ref "U4") (pin "11") (pinfunction "DIN_11") (pintype "bidirectional"))
      (node (ref "U8") (pin "4") (pinfunction "DI_4") (pintype "input"))
    )
    (net (code "23") (name "DOUT") (class "Default")
      (node (ref "SJ3") (pin "3") (pinfunction "3_3") (pintype "passive"))
      (node (ref "U4") (pin "13") (pinfunction "DOUT_13") (pintype "bidirectional"))
    )
    (net (code "24") (name "DRAIN") (class "Default")
      (node (ref "C10") (pin "2") (pinfunction "P$2_2") (pintype "passive"))
      (node (ref "Q6") (pin "3") (pinfunction "D_3") (pintype "passive"))
      (node (ref "R13") (pin "2") (pinfunction "2_2") (pintype "passive"))
    )
    (net (code "25") (name "FB") (class "Default")
      (node (ref "R18") (pin "1") (pinfunction "1_1") (pintype "passive"))
      (node (ref "R19") (pin "2") (pinfunction "2_2") (pintype "passive"))
      (node (ref "TP8") (pin "TP") (pinfunction "TP_TP") (pintype "input"))
      (node (ref "U3") (pin "8") (pinfunction "FB_8") (pintype "input"))
    )
    (net (code "26") (name "FREQ") (class "Default")
      (node (ref "R15") (pin "2") (pinfunction "2_2") (pintype "passive"))
      (node (ref "TP12") (pin "TP") (pinfunction "TP_TP") (pintype "input"))
      (node (ref "U3") (pin "9") (pinfunction "FREQ_9") (pintype "input"))
    )
    (net (code "27") (name "GATE") (class "Default")
      (node (ref "Q2") (pin "1") (pinfunction "G_1") (pintype "passive"))
      (node (ref "Q3") (pin "1") (pinfunction "G_1") (pintype "passive"))
      (node (ref "U7") (pin "8") (pinfunction "GATE_8") (pintype "output"))
    )
    (net (code "28") (name "GND") (class "Default")
      (node (ref "C10") (pin "1") (pinfunction "P$1_1") (pintype "passive"))
      (node (ref "C11") (pin "2") (pinfunction "P$2_2") (pintype "passive"))
      (node (ref "C13") (pin "2") (pinfunction "P$2_2") (pintype "passive"))
      (node (ref "C14") (pin "2") (pinfunction "P$2_2") (pintype "passive"))
      (node (ref "C15") (pin "2") (pinfunction "P$2_2") (pintype "passive"))
      (node (ref "C16") (pin "2") (pinfunction "P$2_2") (pintype "passive"))
      (node (ref "C17") (pin "2") (pinfunction "P$2_2") (pintype "passive"))
      (node (ref "C18") (pin "2") (pinfunction "P$2_2") (pintype "passive"))
      (node (ref "C19") (pin "2") (pinfunction "P$2_2") (pintype "passive"))
      (node (ref "C3") (pin "2") (pinfunction "P$2_2") (pintype "passive"))
      (node (ref "C4") (pin "2") (pinfunction "P$2_2") (pintype "passive"))
      (node (ref "C5") (pin "2") (pinfunction "P$2_2") (pintype "passive"))
      (node (ref "C6") (pin "2") (pinfunction "P$2_2") (pintype "passive"))
      (node (ref "C7") (pin "2") (pinfunction "P$2_2") (pintype "passive"))
      (node (ref "C8") (pin "2") (pinfunction "P$2_2") (pintype "passive"))
      (node (ref "C9") (pin "2") (pinfunction "P$2_2") (pintype "passive"))
      (node (ref "D2") (pin "A") (pinfunction "A_A") (pintype "passive"))
      (node (ref "D4") (pin "2") (pinfunction "2_2") (pintype "passive"))
      (node (ref "D5") (pin "2") (pinfunction "2_2") (pintype "passive"))
      (node (ref "D6") (pin "1") (pinfunction "1_1") (pintype "passive"))
      (node (ref "D7") (pin "2") (pinfunction "2_2") (pintype "passive"))
      (node (ref "IC1") (pin "2") (pinfunction "GND_2") (pintype "bidirectional"))
      (node (ref "IC2") (pin "6") (pinfunction "GND_6") (pintype "power_in"))
      (node (ref "PAD5") (pin "1") (pinfunction "P_1") (pintype "passive"))
      (node (ref "R11") (pin "1") (pinfunction "1_1") (pintype "passive"))
      (node (ref "R14") (pin "2") (pinfunction "2_2") (pintype "passive"))
      (node (ref "R15") (pin "1") (pinfunction "1_1") (pintype "passive"))
      (node (ref "R19") (pin "1") (pinfunction "1_1") (pintype "passive"))
      (node (ref "R21") (pin "2") (pinfunction "2_2") (pintype "passive"))
      (node (ref "R23") (pin "1") (pinfunction "1_1") (pintype "passive"))
      (node (ref "R29") (pin "2") (pinfunction "2_2") (pintype "passive"))
      (node (ref "R7") (pin "1") (pinfunction "1_1") (pintype "passive"))
      (node (ref "U1") (pin "4") (pinfunction "GND_4") (pintype "bidirectional"))
      (node (ref "U2") (pin "13") (pinfunction "A0_13") (pintype "input"))
      (node (ref "U2") (pin "14") (pinfunction "A1_14") (pintype "input"))
      (node (ref "U2") (pin "15") (pinfunction "A2_15") (pintype "input"))
      (node (ref "U2") (pin "16") (pinfunction "A3_16") (pintype "input"))
      (node (ref "U2") (pin "5") (pinfunction "V-REF-L_5") (pintype "input"))
      (node (ref "U2") (pin "6") (pinfunction "GND_6") (pintype "power_in"))
      (node (ref "U2") (pin "9") (pinfunction "LDAC_9") (pintype "input"))
      (node (ref "U3") (pin "10") (pinfunction "NC_10") (pintype "power_in"))
      (node (ref "U3") (pin "11") (pinfunction "PGND_11") (pintype "power_in"))
      (node (ref "U3") (pin "12") (pinfunction "PGND_12") (pintype "power_in"))
      (node (ref "U3") (pin "13") (pinfunction "PGND_13") (pintype "power_in"))
      (node (ref "U3") (pin "14") (pinfunction "NC_14") (pintype "power_in"))
      (node (ref "U3") (pin "17") (pinfunction "POWERPAD_17") (pintype "power_in"))
      (node (ref "U3") (pin "5") (pinfunction "SYNC_5") (pintype "input"))
      (node (ref "U4") (pin "1") (pinfunction "\\~{EN}_1") (pintype "bidirectional"))
      (node (ref "U4") (pin "14") (pinfunction "GND_14") (pintype "bidirectional"))
      (node (ref "U5") (pin "3") (pinfunction "VSS_3") (pintype "power_in"))
      (node (ref "U5") (pin "6") (pinfunction "SDO/AD0_6") (pintype "bidirectional"))
      (node (ref "U5") (pin "8") (pinfunction "RESV_8") (pintype "passive"))
      (node (ref "U5") (pin "9") (pinfunction "RESV_9") (pintype "passive"))
      (node (ref "U6") (pin "10") (pinfunction "GND_10") (pintype "power_in"))
      (node (ref "U6") (pin "11") (pinfunction "PAD_11") (pintype "bidirectional"))
      (node (ref "U6") (pin "9") (pinfunction "OD_9") (pintype "input"))
      (node (ref "U7") (pin "4") (pinfunction "GND_4") (pintype "power_in"))
      (node (ref "U8") (pin "5") (pinfunction "GND_5") (pintype "passive"))
      (node (ref "X2") (pin "2") (pinfunction "K_2") (pintype "passive"))
    )
    (net (code "29") (name "IS") (class "Default")
      (node (ref "Q5") (pin "2") (pinfunction "E_2") (pintype "passive"))
      (node (ref "R10") (pin "1") (pinfunction "1_1") (pintype "passive"))
      (node (ref "U6") (pin "2") (pinfunction "IS_2") (pintype "power_in"))
    )
    (net (code "30") (name "LOAD") (class "Default")
      (node (ref "D6") (pin "2") (pinfunction "2_2") (pintype "passive"))
      (node (ref "R13") (pin "1") (pinfunction "1_1") (pintype "passive"))
      (node (ref "R14") (pin "1") (pinfunction "1_1") (pintype "passive"))
      (node (ref "SJ1") (pin "3") (pinfunction "3_3") (pintype "passive"))
    )
    (net (code "31") (name "MISO") (class "Default")
      (node (ref "PAD2") (pin "1") (pinfunction "P_1") (pintype "passive"))
      (node (ref "SJ6") (pin "2") (pinfunction "2_2") (pintype "passive"))
    )
    (net (code "32") (name "MOSI") (class "Default")
      (node (ref "PAD3") (pin "1") (pinfunction "P_1") (pintype "passive"))
      (node (ref "SJ5") (pin "2") (pinfunction "2_2") (pintype "passive"))
    )
    (net (code "33") (name "Net-(C12-P$2)") (class "Default")
      (node (ref "C12") (pin "2") (pinfunction "P$2_2") (pintype "passive"))
      (node (ref "IC2") (pin "1") (pinfunction "BOOT_1") (pintype "output"))
    )
    (net (code "34") (name "Net-(C15-P$1)") (class "Default")
      (node (ref "C15") (pin "1") (pinfunction "P$1_1") (pintype "passive"))
      (node (ref "R16") (pin "1") (pinfunction "1_1") (pintype "passive"))
    )
    (net (code "35") (name "Net-(Q2-S)") (class "Default")
      (node (ref "Q2") (pin "2") (pinfunction "S_2") (pintype "passive"))
      (node (ref "Q3") (pin "2") (pinfunction "S_2") (pintype "passive"))
    )
    (net (code "36") (name "Net-(R4-Pad1)") (class "Default")
      (node (ref "R4") (pin "1") (pinfunction "1_1") (pintype "passive"))
      (node (ref "R5") (pin "2") (pinfunction "2_2") (pintype "passive"))
    )
    (net (code "37") (name "Net-(R5-Pad1)") (class "Default")
      (node (ref "R5") (pin "1") (pinfunction "1_1") (pintype "passive"))
      (node (ref "R6") (pin "2") (pinfunction "2_2") (pintype "passive"))
    )
    (net (code "38") (name "Net-(R11-Pad2)") (class "Default")
      (node (ref "R11") (pin "2") (pinfunction "2_2") (pintype "passive"))
      (node (ref "R12") (pin "1") (pinfunction "1_1") (pintype "passive"))
    )
    (net (code "39") (name "Net-(R17-Pad1)") (class "Default")
      (node (ref "R17") (pin "1") (pinfunction "1_1") (pintype "passive"))
      (node (ref "R18") (pin "2") (pinfunction "2_2") (pintype "passive"))
    )
    (net (code "40") (name "OV") (class "Default")
      (node (ref "R6") (pin "1") (pinfunction "1_1") (pintype "passive"))
      (node (ref "R7") (pin "2") (pinfunction "2_2") (pintype "passive"))
      (node (ref "TP9") (pin "TP") (pinfunction "TP_TP") (pintype "input"))
      (node (ref "U7") (pin "3") (pinfunction "OV_3") (pintype "input"))
    )
    (net (code "41") (name "PH") (class "Default")
      (node (ref "C12") (pin "1") (pinfunction "P$1_1") (pintype "passive"))
      (node (ref "D2") (pin "C") (pinfunction "C_C") (pintype "passive"))
      (node (ref "IC2") (pin "8") (pinfunction "PH_8") (pintype "output"))
      (node (ref "L2") (pin "1") (pinfunction "1_1") (pintype "passive"))
    )
    (net (code "42") (name "RESET") (class "Default")
      (node (ref "PAD6") (pin "1") (pinfunction "P_1") (pintype "passive"))
      (node (ref "U1") (pin "1") (pinfunction "PB5(NRES)_1") (pintype "bidirectional"))
    )
    (net (code "43") (name "RIN") (class "Default")
      (node (ref "SJ9") (pin "2") (pinfunction "2_2") (pintype "passive"))
      (node (ref "U4") (pin "8") (pinfunction "RIN_8") (pintype "bidirectional"))
    )
    (net (code "44") (name "ROUT") (class "Default")
      (node (ref "R24") (pin "1") (pinfunction "1_1") (pintype "passive"))
      (node (ref "SJ10") (pin "2") (pinfunction "2_2") (pintype "passive"))
      (node (ref "U4") (pin "9") (pinfunction "ROUT_9") (pintype "bidirectional"))
      (node (ref "U8") (pin "1") (pinfunction "RO_1") (pintype "output"))
    )
    (net (code "45") (name "SCK") (class "Default")
      (node (ref "PAD4") (pin "1") (pinfunction "P_1") (pintype "passive"))
      (node (ref "SJ7") (pin "2") (pinfunction "2_2") (pintype "passive"))
    )
    (net (code "46") (name "SCL_3V3") (class "Default")
      (node (ref "Q4") (pin "2") (pinfunction "S_2") (pintype "bidirectional"))
      (node (ref "R22") (pin "1") (pinfunction "1_1") (pintype "passive"))
      (node (ref "SJ4") (pin "2") (pinfunction "2_2") (pintype "passive"))
      (node (ref "U5") (pin "2") (pinfunction "SCL_2") (pintype "input"))
    )
    (net (code "47") (name "SCL_5V0") (class "Default")
      (node (ref "Q4") (pin "3") (pinfunction "D_3") (pintype "bidirectional"))
      (node (ref "R2") (pin "1") (pinfunction "1_1") (pintype "passive"))
      (node (ref "U2") (pin "10") (pinfunction "SCK_10") (pintype "bidirectional"))
    )
    (net (code "48") (name "SDA_3V3") (class "Default")
      (node (ref "Q1") (pin "2") (pinfunction "S_2") (pintype "bidirectional"))
      (node (ref "R20") (pin "1") (pinfunction "1_1") (pintype "passive"))
      (node (ref "SJ12") (pin "2") (pinfunction "2_2") (pintype "passive"))
      (node (ref "U5") (pin "4") (pinfunction "SDA/SDIO/SDI_4") (pintype "bidirectional"))
    )
    (net (code "49") (name "SDA_5V0") (class "Default")
      (node (ref "Q1") (pin "3") (pinfunction "D_3") (pintype "bidirectional"))
      (node (ref "R1") (pin "1") (pinfunction "1_1") (pintype "passive"))
      (node (ref "U2") (pin "11") (pinfunction "SDA_11") (pintype "bidirectional"))
    )
    (net (code "50") (name "SET") (class "Default")
      (node (ref "R21") (pin "1") (pinfunction "1_1") (pintype "passive"))
      (node (ref "U6") (pin "7") (pinfunction "SET_7") (pintype "bidirectional"))
    )
    (net (code "51") (name "SHDN") (class "Default")
      (node (ref "R8") (pin "1") (pinfunction "1_1") (pintype "passive"))
      (node (ref "U7") (pin "5") (pinfunction "*SHDN_5") (pintype "input"))
    )
    (net (code "52") (name "SS") (class "Default")
      (node (ref "C6") (pin "1") (pinfunction "P$1_1") (pintype "passive"))
      (node (ref "TP11") (pin "TP") (pinfunction "TP_TP") (pintype "input"))
      (node (ref "U3") (pin "4") (pinfunction "SS_4") (pintype "input"))
    )
    (net (code "53") (name "SW") (class "Default")
      (node (ref "D1") (pin "A") (pinfunction "A_A") (pintype "passive"))
      (node (ref "L1") (pin "2") (pinfunction "2_2") (pintype "passive"))
      (node (ref "U3") (pin "1") (pinfunction "SW_1") (pintype "output"))
      (node (ref "U3") (pin "15") (pinfunction "SW_15") (pintype "output"))
      (node (ref "U3") (pin "16") (pinfunction "SW_16") (pintype "output"))
    )
    (net (code "54") (name "UV") (class "Default")
      (node (ref "R3") (pin "1") (pinfunction "1_1") (pintype "passive"))
      (node (ref "R4") (pin "2") (pinfunction "2_2") (pintype "passive"))
      (node (ref "TP10") (pin "TP") (pinfunction "TP_TP") (pintype "input"))
      (node (ref "U7") (pin "2") (pinfunction "UV_2") (pintype "input"))
    )
    (net (code "55") (name "V+") (class "Default")
      (node (ref "C3") (pin "1") (pinfunction "P$1_1") (pintype "passive"))
      (node (ref "U4") (pin "3") (pinfunction "V+_3") (pintype "bidirectional"))
    )
    (net (code "56") (name "V-") (class "Default")
      (node (ref "C4") (pin "1") (pinfunction "P$1_1") (pintype "passive"))
      (node (ref "U4") (pin "7") (pinfunction "V-_7") (pintype "bidirectional"))
    )
    (net (code "57") (name "V-OUT-1") (class "Default")
      (node (ref "TP5") (pin "TP") (pinfunction "TP_TP") (pintype "input"))
      (node (ref "U2") (pin "8") (pinfunction "V-OUT-D_8") (pintype "output"))
      (node (ref "U6") (pin "6") (pinfunction "VIN_6") (pintype "input"))
    )
    (net (code "58") (name "V-OUT-2") (class "Default")
      (node (ref "D7") (pin "1") (pinfunction "1_1") (pintype "passive"))
      (node (ref "SJ1") (pin "1") (pinfunction "1_1") (pintype "passive"))
      (node (ref "TP6") (pin "TP") (pinfunction "TP_TP") (pintype "input"))
      (node (ref "U2") (pin "2") (pinfunction "V-OUT-B_2") (pintype "output"))
    )
    (net (code "59") (name "VG") (class "Default")
      (node (ref "Q5") (pin "3") (pinfunction "C_3") (pintype "passive"))
      (node (ref "Q6") (pin "1") (pinfunction "G_1") (pintype "passive"))
      (node (ref "U6") (pin "3") (pinfunction "VG_3") (pintype "bidirectional"))
    )
    (net (code "60") (name "VIN") (class "Default")
      (node (ref "Q2") (pin "3") (pinfunction "D_3") (pintype "passive"))
      (node (ref "R3") (pin "2") (pinfunction "2_2") (pintype "passive"))
      (node (ref "R8") (pin "2") (pinfunction "2_2") (pintype "passive"))
      (node (ref "U7") (pin "1") (pinfunction "VIN_1") (pintype "input"))
      (node (ref "X2") (pin "1") (pinfunction "K_1") (pintype "passive"))
    )
    (net (code "61") (name "VIN_5V0") (class "Default")
      (node (ref "C9") (pin "1") (pinfunction "P$1_1") (pintype "passive"))
      (node (ref "D3") (pin "C") (pinfunction "C_C") (pintype "passive"))
      (node (ref "IC1") (pin "1") (pinfunction "VIN_1") (pintype "bidirectional"))
      (node (ref "IC1") (pin "3") (pinfunction "EN_3") (pintype "bidirectional"))
      (node (ref "TP2") (pin "TP") (pinfunction "TP_TP") (pintype "input"))
    )
    (net (code "62") (name "VIN_30") (class "Default")
      (node (ref "C11") (pin "1") (pinfunction "P$1_1") (pintype "passive"))
      (node (ref "IC2") (pin "7") (pinfunction "VIN_7") (pintype "input"))
      (node (ref "Q3") (pin "3") (pinfunction "D_3") (pintype "passive"))
      (node (ref "U7") (pin "7") (pinfunction "VOUT_7") (pintype "output"))
    )
    (net (code "63") (name "VSENSE") (class "Default")
      (node (ref "IC2") (pin "4") (pinfunction "VSENSE_4") (pintype "input"))
      (node (ref "R12") (pin "2") (pinfunction "2_2") (pintype "passive"))
      (node (ref "R9") (pin "1") (pinfunction "1_1") (pintype "passive"))
      (node (ref "TP7") (pin "TP") (pinfunction "TP_TP") (pintype "input"))
    )
    (net (code "64") (name "unconnected-(IC1-BYP-Pad4)") (class "Default")
      (node (ref "IC1") (pin "4") (pinfunction "BYP_4") (pintype "bidirectional"))
    )
    (net (code "65") (name "unconnected-(IC2-ENA-Pad5)") (class "Default")
      (node (ref "IC2") (pin "5") (pinfunction "ENA_5") (pintype "input"))
    )
    (net (code "66") (name "unconnected-(U2-V-OUT-A-Pad1)") (class "Default")
      (node (ref "U2") (pin "1") (pinfunction "V-OUT-A_1") (pintype "output"))
    )
    (net (code "67") (name "unconnected-(U2-V-OUT-C-Pad7)") (class "Default")
      (node (ref "U2") (pin "7") (pinfunction "V-OUT-C_7") (pintype "output"))
    )
    (net (code "68") (name "unconnected-(U3-AGND-Pad6)") (class "Default")
      (node (ref "U3") (pin "6") (pinfunction "AGND_6") (pintype "power_in"))
    )
    (net (code "69") (name "unconnected-(U4-\\~{INV}-Pad10)") (class "Default")
      (node (ref "U4") (pin "10") (pinfunction "\\~{INV}_10") (pintype "bidirectional"))
    )
    (net (code "70") (name "unconnected-(U5-INT-Pad7)") (class "Default")
      (node (ref "U5") (pin "7") (pinfunction "INT_7") (pintype "output"))
    )
    (net (code "71") (name "unconnected-(U6-EF-Pad8)") (class "Default")
      (node (ref "U6") (pin "8") (pinfunction "EF_8") (pintype "bidirectional"))
    )
    (net (code "72") (name "unconnected-(U6-REGF-Pad5)") (class "Default")
      (node (ref "U6") (pin "5") (pinfunction "REGF_5") (pintype "bidirectional"))
    )
    (net (code "73") (name "unconnected-(U6-REGS-Pad4)") (class "Default")
      (node (ref "U6") (pin "4") (pinfunction "REGS_4") (pintype "input"))
    )
    (net (code "74") (name "unconnected-(U7-*FAULT-Pad6)") (class "Default")
      (node (ref "U7") (pin "6") (pinfunction "*FAULT_6") (pintype "output"))
    )
  )
)
